# 07_RFID_LCD.net
KiCad netlist of a schematic drawn in Altium Designer
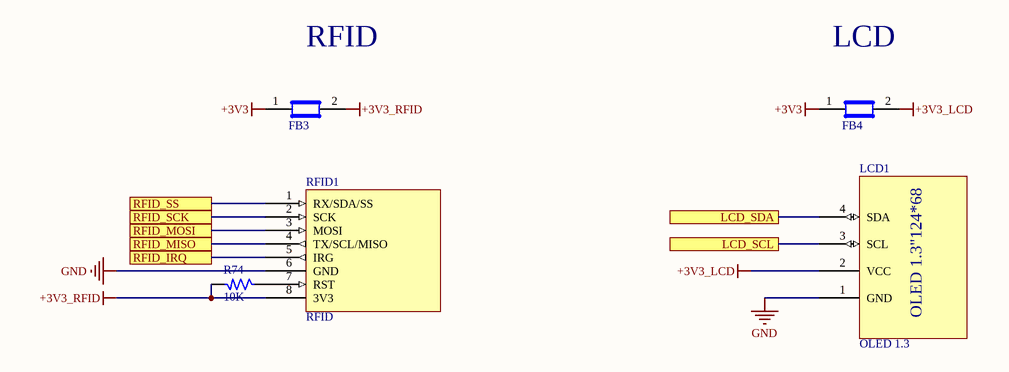
[diagram p0: [07]RFID_LCD.SchDoc]

(export (version "E")
  (design (tool "Eeschema 10.0.6"))
  (components
    (comp (ref "FB3")
      (value "BLM21PG600SN1D")
      (footprint "R0805")
      (description "Ferrite Bead")
      (libsource (lib "GPS_Traking_V1_1") (part "Ferrite Bead"))
    )
    (comp (ref "FB4")
      (value "BLM21PG600SN1D")
      (footprint "R0805")
      (description "Ferrite Bead")
      (libsource (lib "GPS_Traking_V1_1") (part "Ferrite Bead"))
    )
    (comp (ref "LCD1")
      (value "OLED 1.3")
      (footprint "CON_4P")
      (libsource (lib "My Library") (part "OLED 1.3"))
    )
    (comp (ref "R74")
      (value "10K")
      (footprint "RES-SMD-0805")
      (description "Resistor SMD")
      (libsource (lib "GPS_Traking_V1_1") (part "RM"))
    )
    (comp (ref "RFID1")
      (value "RFID")
      (footprint "RFID RC522")
      (libsource (lib "My Library") (part "RFID RC522"))
    )
  )
  (nets
    (net (code "1") (name "+3V3") (class "Default")
      (node (ref "FB3") (pin "1") (pinfunction "1_1") (pintype "passive"))
      (node (ref "FB4") (pin "1") (pinfunction "1_1") (pintype "passive"))
    )
    (net (code "2") (name "+3V3_LCD") (class "Default")
      (node (ref "FB4") (pin "2") (pinfunction "2_2") (pintype "passive"))
      (node (ref "LCD1") (pin "2") (pinfunction "VCC_2") (pintype "power_in"))
    )
    (net (code "3") (name "+3V3_RFID") (class "Default")
      (node (ref "FB3") (pin "2") (pinfunction "2_2") (pintype "passive"))
      (node (ref "R74") (pin "2") (pinfunction "2_2") (pintype "passive"))
      (node (ref "RFID1") (pin "8") (pinfunction "3V3_8") (pintype "power_in"))
    )
    (net (code "4") (name "/LCD_SCL") (class "Default")
      (node (ref "LCD1") (pin "3") (pinfunction "SCL_3") (pintype "bidirectional"))
    )
    (net (code "5") (name "/LCD_SDA") (class "Default")
      (node (ref "LCD1") (pin "4") (pinfunction "SDA_4") (pintype "bidirectional"))
    )
    (net (code "6") (name "/RFID_IRQ") (class "Default")
      (node (ref "RFID1") (pin "5") (pinfunction "IRG_5") (pintype "output"))
    )
    (net (code "7") (name "/RFID_MISO") (class "Default")
      (node (ref "RFID1") (pin "4") (pinfunction "TX/SCL/MISO_4") (pintype "output"))
    )
    (net (code "8") (name "/RFID_MOSI") (class "Default")
      (node (ref "RFID1") (pin "3") (pinfunction "MOSI_3") (pintype "input"))
    )
    (net (code "9") (name "/RFID_SCK") (class "Default")
      (node (ref "RFID1") (pin "2") (pinfunction "SCK_2") (pintype "input"))
    )
    (net (code "10") (name "/RFID_SS") (class "Default")
      (node (ref "RFID1") (pin "1") (pinfunction "RX/SDA/SS_1") (pintype "input"))
    )
    (net (code "11") (name "GND") (class "Default")
      (node (ref "LCD1") (pin "1") (pinfunction "GND_1") (pintype "power_in"))
      (node (ref "RFID1") (pin "6") (pinfunction "GND_6") (pintype "power_in"))
    )
    (net (code "12") (name "Net-(RFID1-RST)") (class "Default")
      (node (ref "R74") (pin "1") (pinfunction "1_1") (pintype "passive"))
      (node (ref "RFID1") (pin "7") (pinfunction "RST_7") (pintype "input"))
    )
  )
)
